# keyDuino_v5_rev1.net
KiCad netlist of a schematic drawn in EAGLE
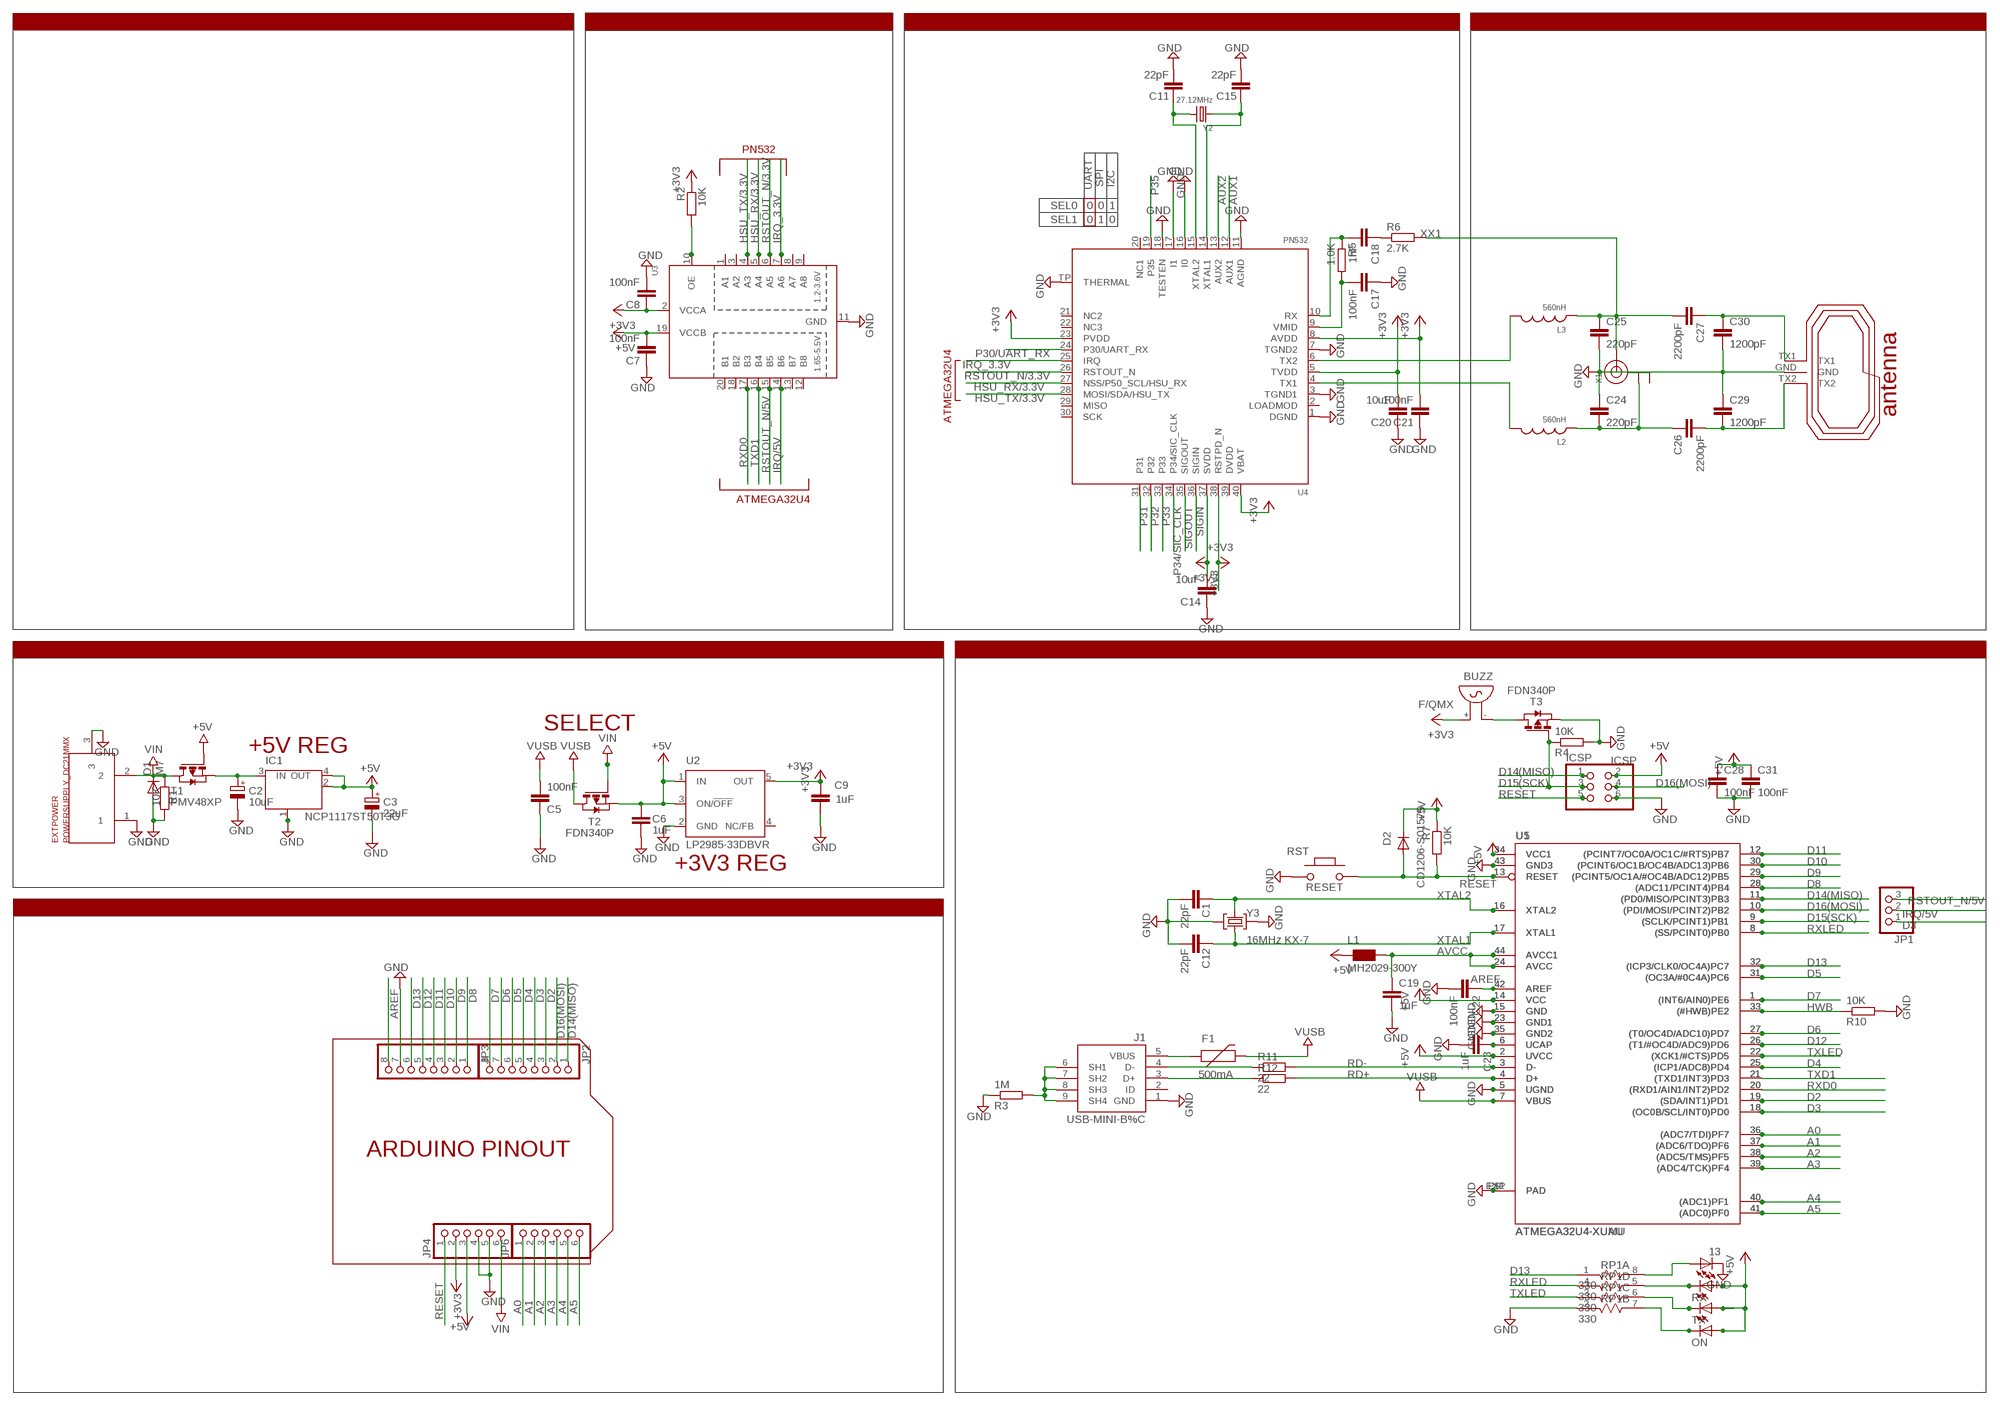
[diagram p0: schematic, sheet 1]

(export (version "E")
  (design (tool "Eeschema 10.0.6"))
  (components
    (comp (ref "13")
      (value "LEDCHIPLED_0603")
      (footprint "eagle-import:CHIPLED_0603")
      (libsource (lib "eagle-import") (part "LEDCHIPLED_0603"))
    )
    (comp (ref "BUZZ")
      (value "F/QMX")
      (footprint "eagle-import:F_QMX")
      (libsource (lib "eagle-import") (part "F/QMX"))
    )
    (comp (ref "C1")
      (value "22pF")
      (footprint "eagle-import:0603-CAP")
      (libsource (lib "eagle-import") (part "CAP0603-CAP"))
    )
    (comp (ref "C2")
      (value "10uF")
      (footprint "eagle-import:SMC_B")
      (libsource (lib "eagle-import") (part "CPOL-EUSMCB"))
    )
    (comp (ref "C3")
      (value "22uF")
      (footprint "eagle-import:SMC_B")
      (libsource (lib "eagle-import") (part "CPOL-EUSMCB"))
    )
    (comp (ref "C5")
      (value "100nF")
      (footprint "eagle-import:C0603")
      (libsource (lib "eagle-import") (part "resistor_C-EUC0603"))
    )
    (comp (ref "C6")
      (value "1uF")
      (footprint "eagle-import:C0603")
      (libsource (lib "eagle-import") (part "C-EUC0603"))
    )
    (comp (ref "C7")
      (value "100nF")
      (footprint "eagle-import:C0603")
      (libsource (lib "eagle-import") (part "C-EUC0603"))
    )
    (comp (ref "C8")
      (value "100nF")
      (footprint "eagle-import:C0603")
      (libsource (lib "eagle-import") (part "C-EUC0603"))
    )
    (comp (ref "C9")
      (value "1uF")
      (footprint "eagle-import:C0603")
      (libsource (lib "eagle-import") (part "C-EUC0603"))
    )
    (comp (ref "C11")
      (value "22pF")
      (footprint "eagle-import:0603-CAP")
      (libsource (lib "eagle-import") (part "CAP0603-CAP"))
    )
    (comp (ref "C12")
      (value "22pF")
      (footprint "eagle-import:0603-CAP")
      (libsource (lib "eagle-import") (part "CAP0603-CAP"))
    )
    (comp (ref "C14")
      (value "10uF")
      (footprint "eagle-import:C0805")
      (libsource (lib "eagle-import") (part "C-EUC0805"))
    )
    (comp (ref "C15")
      (value "22pF")
      (footprint "eagle-import:0603-CAP")
      (libsource (lib "eagle-import") (part "CAP0603-CAP"))
    )
    (comp (ref "C17")
      (value "100nF")
      (footprint "eagle-import:C0603")
      (libsource (lib "eagle-import") (part "C-EUC0603"))
    )
    (comp (ref "C18")
      (value "1nF")
      (footprint "eagle-import:C0603")
      (libsource (lib "eagle-import") (part "C-EUC0603"))
    )
    (comp (ref "C19")
      (value "1uF")
      (footprint "eagle-import:C0603")
      (libsource (lib "eagle-import") (part "resistor_C-EUC0603"))
    )
    (comp (ref "C20")
      (value "10uF")
      (footprint "eagle-import:C0805")
      (libsource (lib "eagle-import") (part "C-EUC0805"))
    )
    (comp (ref "C21")
      (value "100nF")
      (footprint "eagle-import:C0805")
      (libsource (lib "eagle-import") (part "C-EUC0805"))
    )
    (comp (ref "C22")
      (value "100nF")
      (footprint "eagle-import:C0603")
      (libsource (lib "eagle-import") (part "resistor_C-EUC0603"))
    )
    (comp (ref "C23")
      (value "1uF")
      (footprint "eagle-import:C0603")
      (libsource (lib "eagle-import") (part "resistor_C-EUC0603"))
    )
    (comp (ref "C24")
      (value "220pF")
      (footprint "eagle-import:C0603")
      (libsource (lib "eagle-import") (part "C-EUC0603"))
    )
    (comp (ref "C25")
      (value "220pF")
      (footprint "eagle-import:C0603")
      (libsource (lib "eagle-import") (part "C-EUC0603"))
    )
    (comp (ref "C26")
      (value "2200pF")
      (footprint "eagle-import:C0603")
      (libsource (lib "eagle-import") (part "C-EUC0603"))
    )
    (comp (ref "C27")
      (value "2200pF")
      (footprint "eagle-import:C0603")
      (libsource (lib "eagle-import") (part "C-EUC0603"))
    )
    (comp (ref "C28")
      (value "100nF")
      (footprint "eagle-import:C0603")
      (libsource (lib "eagle-import") (part "resistor_C-EUC0603"))
    )
    (comp (ref "C29")
      (value "1200pF")
      (footprint "eagle-import:C0603")
      (libsource (lib "eagle-import") (part "C-EUC0603"))
    )
    (comp (ref "C30")
      (value "1200pF")
      (footprint "eagle-import:C0603")
      (libsource (lib "eagle-import") (part "C-EUC0603"))
    )
    (comp (ref "C31")
      (value "100nF")
      (footprint "eagle-import:C0603")
      (libsource (lib "eagle-import") (part "resistor_C-EUC0603"))
    )
    (comp (ref "D1")
      (value "M7")
      (footprint "eagle-import:SMB")
      (libsource (lib "eagle-import") (part "DIODE-SMB"))
    )
    (comp (ref "D2")
      (value "CD1206-S01575")
      (footprint "eagle-import:MINIMELF")
      (libsource (lib "eagle-import") (part "DIODE-MINIMELF"))
    )
    (comp (ref "EXTPOWER")
      (value "POWERSUPPLY_DC21MMX")
      (footprint "eagle-import:POWERSUPPLY_DC-21MM")
      (libsource (lib "eagle-import") (part "POWERSUPPLY_DC21MMX"))
    )
    (comp (ref "F1")
      (value "500mA")
      (footprint "eagle-import:PTC-1206")
      (libsource (lib "eagle-import") (part "PTCSMD"))
    )
    (comp (ref "IC1")
      (value "NCP1117ST50T3G")
      (footprint "eagle-import:SOT223")
      (libsource (lib "eagle-import") (part "MC33269ST-3.3T3"))
    )
    (comp (ref "ICSP")
      (value "ICSP")
      (footprint "eagle-import:2X03")
      (libsource (lib "eagle-import") (part "PINHD-2X3"))
    )
    (comp (ref "J1")
      (value "USB-MINI-B%C")
      (footprint "eagle-import:USB-MINI-B_2")
      (libsource (lib "eagle-import") (part "USB-MINI-B%C"))
    )
    (comp (ref "JP1")
      (value "PINHD-1X3")
      (footprint "eagle-import:1X03")
      (libsource (lib "eagle-import") (part "PINHD-1X3"))
    )
    (comp (ref "JP2")
      (value "PINHD-1X8CLEANBIG")
      (footprint "eagle-import:1X08-CLEANBIG")
      (libsource (lib "eagle-import") (part "PINHD-1X8CLEANBIG"))
    )
    (comp (ref "JP3")
      (value "PINHD-1X8CLEANBIG")
      (footprint "eagle-import:1X08-CLEANBIG")
      (libsource (lib "eagle-import") (part "PINHD-1X8CLEANBIG"))
    )
    (comp (ref "JP4")
      (value "PINHD-1X6CB")
      (footprint "eagle-import:1X06-CLEANBIG")
      (libsource (lib "eagle-import") (part "PINHD-1X6CB"))
    )
    (comp (ref "JP6")
      (value "PINHD-1X6CB")
      (footprint "eagle-import:1X06-CLEANBIG")
      (libsource (lib "eagle-import") (part "PINHD-1X6CB"))
    )
    (comp (ref "L1")
      (value "MH2029-300Y")
      (footprint "eagle-import:0805")
      (libsource (lib "eagle-import") (part "WE-CBF_0805"))
    )
    (comp (ref "L2")
      (value "560nH")
      (footprint "eagle-import:0805@1")
      (libsource (lib "eagle-import") (part "INDUCTOR0805"))
    )
    (comp (ref "L3")
      (value "560nH")
      (footprint "eagle-import:0805@1")
      (libsource (lib "eagle-import") (part "INDUCTOR0805"))
    )
    (comp (ref "ON")
      (value "LEDCHIPLED_0603")
      (footprint "eagle-import:CHIPLED_0603")
      (libsource (lib "eagle-import") (part "LEDCHIPLED_0603"))
    )
    (comp (ref "R1")
      (value "10K")
      (footprint "eagle-import:R0603")
      (libsource (lib "eagle-import") (part "resistor_R-EU_R0603"))
    )
    (comp (ref "R2")
      (value "10K")
      (footprint "eagle-import:R0603")
      (libsource (lib "eagle-import") (part "R-EU_R0603"))
    )
    (comp (ref "R3")
      (value "1M")
      (footprint "eagle-import:R0805")
      (libsource (lib "eagle-import") (part "R-EU_R0805"))
    )
    (comp (ref "R4")
      (value "10K")
      (footprint "eagle-import:R0603")
      (libsource (lib "eagle-import") (part "R-EU_R0603"))
    )
    (comp (ref "R5")
      (value "1.0K")
      (footprint "eagle-import:R0603")
      (libsource (lib "eagle-import") (part "R-EU_R0603"))
    )
    (comp (ref "R6")
      (value "2.7K")
      (footprint "eagle-import:R0603")
      (libsource (lib "eagle-import") (part "R-EU_R0603"))
    )
    (comp (ref "R7")
      (value "10K")
      (footprint "eagle-import:R0603")
      (libsource (lib "eagle-import") (part "R-EU_R0603"))
    )
    (comp (ref "R10")
      (value "10K")
      (footprint "eagle-import:R0603")
      (libsource (lib "eagle-import") (part "R-EU_R0603"))
    )
    (comp (ref "R11")
      (value "22")
      (footprint "eagle-import:R0603")
      (libsource (lib "eagle-import") (part "R-EU_R0603"))
    )
    (comp (ref "R12")
      (value "22")
      (footprint "eagle-import:R0603")
      (libsource (lib "eagle-import") (part "R-EU_R0603"))
    )
    (comp (ref "RP1")
      (value "330")
      (footprint "eagle-import:RES4NT")
      (libsource (lib "eagle-import") (part "RES4NT"))
    )
    (comp (ref "RST")
      (value "RESET")
      (footprint "eagle-import:157SW")
      (libsource (lib "eagle-import") (part "PB157"))
    )
    (comp (ref "RX")
      (value "LEDCHIPLED_0603")
      (footprint "eagle-import:CHIPLED_0603")
      (libsource (lib "eagle-import") (part "LEDCHIPLED_0603"))
    )
    (comp (ref "T1")
      (value "PMV48XP")
      (footprint "eagle-import:SOT-23")
      (libsource (lib "eagle-import") (part "PMOSSOT23"))
    )
    (comp (ref "T2")
      (value "FDN340P")
      (footprint "eagle-import:SOT-23")
      (libsource (lib "eagle-import") (part "PMOSSOT23"))
    )
    (comp (ref "T3")
      (value "FDN340P")
      (footprint "eagle-import:SOT-23")
      (libsource (lib "eagle-import") (part "PMOSSOT23"))
    )
    (comp (ref "TX")
      (value "LEDCHIPLED_0603")
      (footprint "eagle-import:CHIPLED_0603")
      (libsource (lib "eagle-import") (part "LEDCHIPLED_0603"))
    )
    (comp (ref "U$1")
      (value "ANT_V3")
      (footprint "eagle-import:ANT_13.56_P4")
      (libsource (lib "eagle-import") (part "ANT_V3"))
    )
    (comp (ref "U1")
      (value "ATMEGA32U4-XUAU")
      (footprint "eagle-import:TQFP44-PAD")
      (libsource (lib "eagle-import") (part "ATMEGA32U4-XUAU"))
    )
    (comp (ref "U2")
      (value "LP2985-33DBVR")
      (footprint "eagle-import:SOT23-DBV")
      (libsource (lib "eagle-import") (part "LP2985-XXDBVR33"))
    )
    (comp (ref "U3")
      (value "TXB0108PWR")
      (footprint "eagle-import:TSSOP20")
      (libsource (lib "eagle-import") (part "TXB0108PWR"))
    )
    (comp (ref "U4")
      (value "PN532")
      (footprint "eagle-import:HVQFN40-6X6")
      (libsource (lib "eagle-import") (part "PN532"))
    )
    (comp (ref "U5")
      (value "ATMEGA32U4-XUMU")
      (footprint "eagle-import:QFN44ML7X7")
      (libsource (lib "eagle-import") (part "ATMEGA32U4-XUMU"))
    )
    (comp (ref "X1")
      (value "ANTENNA_U.FL")
      (footprint "eagle-import:U.FL")
      (libsource (lib "eagle-import") (part "ANTENNA_U.FL"))
    )
    (comp (ref "Y2")
      (value "27.12MHz")
      (footprint "eagle-import:CRYSTAL_3.2X2.5")
      (libsource (lib "eagle-import") (part "CRYSTALTHIN"))
    )
    (comp (ref "Y3")
      (value "16MHz KX-7")
      (footprint "eagle-import:CRYSTAL-3.2-2.5")
      (libsource (lib "eagle-import") (part "CRYSTAL-3.2-2.5"))
    )
  )
  (nets
    (net (code "1") (name "+3V3") (class "Default")
      (node (ref "BUZZ") (pin "+") (pinfunction "2_+") (pintype "passive"))
      (node (ref "C14") (pin "2") (pinfunction "2_2") (pintype "passive"))
      (node (ref "C20") (pin "2") (pinfunction "2_2") (pintype "passive"))
      (node (ref "C21") (pin "2") (pinfunction "2_2") (pintype "passive"))
      (node (ref "C8") (pin "1") (pinfunction "1_1") (pintype "passive"))
      (node (ref "C9") (pin "2") (pinfunction "2_2") (pintype "passive"))
      (node (ref "JP4") (pin "2") (pinfunction "2_2") (pintype "passive"))
      (node (ref "R2") (pin "1") (pinfunction "1_1") (pintype "passive"))
      (node (ref "U2") (pin "5") (pinfunction "OUT_5") (pintype "passive"))
      (node (ref "U3") (pin "2") (pinfunction "VCCA_2") (pintype "bidirectional"))
      (node (ref "U4") (pin "23") (pinfunction "PVDD_23") (pintype "bidirectional"))
      (node (ref "U4") (pin "37") (pinfunction "SVDD_37") (pintype "bidirectional"))
      (node (ref "U4") (pin "38") (pinfunction "RSTPD_N_38") (pintype "bidirectional"))
      (node (ref "U4") (pin "40") (pinfunction "VBAT_40") (pintype "bidirectional"))
      (node (ref "U4") (pin "5") (pinfunction "TVDD_5") (pintype "bidirectional"))
      (node (ref "U4") (pin "8") (pinfunction "AVDD_8") (pintype "bidirectional"))
    )
    (net (code "2") (name "+5V") (class "Default")
      (node (ref "C28") (pin "1") (pinfunction "1_1") (pintype "passive"))
      (node (ref "C3") (pin "+") (pinfunction "+_+") (pintype "passive"))
      (node (ref "C31") (pin "1") (pinfunction "1_1") (pintype "passive"))
      (node (ref "C6") (pin "2") (pinfunction "2_2") (pintype "passive"))
      (node (ref "C7") (pin "2") (pinfunction "2_2") (pintype "passive"))
      (node (ref "D2") (pin "C") (pinfunction "C_C") (pintype "passive"))
      (node (ref "IC1") (pin "2") (pinfunction "OUT_2") (pintype "passive"))
      (node (ref "IC1") (pin "4") (pinfunction "OUT_4") (pintype "passive"))
      (node (ref "ICSP") (pin "2") (pinfunction "2_2") (pintype "passive"))
      (node (ref "JP4") (pin "3") (pinfunction "3_3") (pintype "passive"))
      (node (ref "L1") (pin "1") (pinfunction "1_1") (pintype "passive"))
      (node (ref "ON") (pin "A") (pinfunction "A_A") (pintype "passive"))
      (node (ref "R7") (pin "1") (pinfunction "1_1") (pintype "passive"))
      (node (ref "RX") (pin "A") (pinfunction "A_A") (pintype "passive"))
      (node (ref "T1") (pin "3") (pinfunction "G_3") (pintype "passive"))
      (node (ref "T2") (pin "2") (pinfunction "S_2") (pintype "passive"))
      (node (ref "TX") (pin "A") (pinfunction "A_A") (pintype "passive"))
      (node (ref "U1") (pin "14") (pinfunction "VCC_14") (pintype "power_in"))
      (node (ref "U1") (pin "2") (pinfunction "UVCC_2") (pintype "power_in"))
      (node (ref "U1") (pin "34") (pinfunction "VCC1_34") (pintype "power_in"))
      (node (ref "U2") (pin "1") (pinfunction "IN_1") (pintype "input"))
      (node (ref "U2") (pin "3") (pinfunction "ON/~{OFF}_3") (pintype "input"))
      (node (ref "U3") (pin "19") (pinfunction "VCCB_19") (pintype "bidirectional"))
      (node (ref "U5") (pin "14") (pinfunction "VCC_14") (pintype "power_in"))
      (node (ref "U5") (pin "2") (pinfunction "UVCC_2") (pintype "power_in"))
      (node (ref "U5") (pin "34") (pinfunction "VCC1_34") (pintype "power_in"))
    )
    (net (code "3") (name "/A0") (class "Default")
      (node (ref "JP6") (pin "1") (pinfunction "1_1") (pintype "passive"))
      (node (ref "U1") (pin "36") (pinfunction "(ADC7/TDI)PF7_36") (pintype "bidirectional"))
      (node (ref "U5") (pin "36") (pinfunction "(ADC7/TDI)PF7_36") (pintype "bidirectional"))
    )
    (net (code "4") (name "/A1") (class "Default")
      (node (ref "JP6") (pin "2") (pinfunction "2_2") (pintype "passive"))
      (node (ref "U1") (pin "37") (pinfunction "(ADC6/TDO)PF6_37") (pintype "bidirectional"))
      (node (ref "U5") (pin "37") (pinfunction "(ADC6/TDO)PF6_37") (pintype "bidirectional"))
    )
    (net (code "5") (name "/A2") (class "Default")
      (node (ref "JP6") (pin "3") (pinfunction "3_3") (pintype "passive"))
      (node (ref "U1") (pin "38") (pinfunction "(ADC5/TMS)PF5_38") (pintype "bidirectional"))
      (node (ref "U5") (pin "38") (pinfunction "(ADC5/TMS)PF5_38") (pintype "bidirectional"))
    )
    (net (code "6") (name "/A3") (class "Default")
      (node (ref "JP6") (pin "4") (pinfunction "4_4") (pintype "passive"))
      (node (ref "U1") (pin "39") (pinfunction "(ADC4/TCK)PF4_39") (pintype "bidirectional"))
      (node (ref "U5") (pin "39") (pinfunction "(ADC4/TCK)PF4_39") (pintype "bidirectional"))
    )
    (net (code "7") (name "/A4") (class "Default")
      (node (ref "JP6") (pin "5") (pinfunction "5_5") (pintype "passive"))
      (node (ref "U1") (pin "40") (pinfunction "(ADC1)PF1_40") (pintype "bidirectional"))
      (node (ref "U5") (pin "40") (pinfunction "(ADC1)PF1_40") (pintype "bidirectional"))
    )
    (net (code "8") (name "/A5") (class "Default")
      (node (ref "JP6") (pin "6") (pinfunction "6_6") (pintype "passive"))
      (node (ref "U1") (pin "41") (pinfunction "(ADC0)PF0_41") (pintype "bidirectional"))
      (node (ref "U5") (pin "41") (pinfunction "(ADC0)PF0_41") (pintype "bidirectional"))
    )
    (net (code "9") (name "/AREF") (class "Default")
      (node (ref "C22") (pin "1") (pinfunction "1_1") (pintype "passive"))
      (node (ref "JP3") (pin "8") (pinfunction "8_8") (pintype "passive"))
      (node (ref "U1") (pin "42") (pinfunction "AREF_42") (pintype "power_in"))
      (node (ref "U5") (pin "42") (pinfunction "AREF_42") (pintype "power_in"))
    )
    (net (code "10") (name "/AUX1") (class "Default")
      (node (ref "U4") (pin "12") (pinfunction "AUX1_12") (pintype "bidirectional"))
    )
    (net (code "11") (name "/AUX2") (class "Default")
      (node (ref "U4") (pin "13") (pinfunction "AUX2_13") (pintype "bidirectional"))
    )
    (net (code "12") (name "/AVCC") (class "Default")
      (node (ref "C19") (pin "1") (pinfunction "1_1") (pintype "passive"))
      (node (ref "L1") (pin "2") (pinfunction "2_2") (pintype "passive"))
      (node (ref "U1") (pin "24") (pinfunction "AVCC_24") (pintype "power_in"))
      (node (ref "U1") (pin "44") (pinfunction "AVCC1_44") (pintype "power_in"))
      (node (ref "U5") (pin "24") (pinfunction "AVCC_24") (pintype "power_in"))
      (node (ref "U5") (pin "44") (pinfunction "AVCC1_44") (pintype "power_in"))
    )
    (net (code "13") (name "/D2") (class "Default")
      (node (ref "JP2") (pin "3") (pinfunction "3_3") (pintype "passive"))
      (node (ref "U1") (pin "19") (pinfunction "(SDA/INT1)PD1_19") (pintype "bidirectional"))
      (node (ref "U5") (pin "19") (pinfunction "(SDA/INT1)PD1_19") (pintype "bidirectional"))
    )
    (net (code "14") (name "/D3") (class "Default")
      (node (ref "JP1") (pin "1") (pinfunction "1_1") (pintype "passive"))
      (node (ref "JP2") (pin "4") (pinfunction "4_4") (pintype "passive"))
      (node (ref "U1") (pin "18") (pinfunction "(OC0B/SCL/INT0)PD0_18") (pintype "bidirectional"))
      (node (ref "U5") (pin "18") (pinfunction "(OC0B/SCL/INT0)PD0_18") (pintype "bidirectional"))
    )
    (net (code "15") (name "/D4") (class "Default")
      (node (ref "JP2") (pin "5") (pinfunction "5_5") (pintype "passive"))
      (node (ref "U1") (pin "25") (pinfunction "(ICP1/ADC8)PD4_25") (pintype "bidirectional"))
      (node (ref "U5") (pin "25") (pinfunction "(ICP1/ADC8)PD4_25") (pintype "bidirectional"))
    )
    (net (code "16") (name "/D5") (class "Default")
      (node (ref "JP2") (pin "6") (pinfunction "6_6") (pintype "passive"))
      (node (ref "U1") (pin "31") (pinfunction "(OC3A/#0C4A)PC6_31") (pintype "bidirectional"))
      (node (ref "U5") (pin "31") (pinfunction "(OC3A/#0C4A)PC6_31") (pintype "bidirectional"))
    )
    (net (code "17") (name "/D6") (class "Default")
      (node (ref "JP2") (pin "7") (pinfunction "7_7") (pintype "passive"))
      (node (ref "U1") (pin "27") (pinfunction "(T0/OC4D/ADC10)PD7_27") (pintype "bidirectional"))
      (node (ref "U5") (pin "27") (pinfunction "(T0/OC4D/ADC10)PD7_27") (pintype "bidirectional"))
    )
    (net (code "18") (name "/D7") (class "Default")
      (node (ref "JP2") (pin "8") (pinfunction "8_8") (pintype "passive"))
      (node (ref "U1") (pin "1") (pinfunction "(INT6/AIN0)PE6_1") (pintype "bidirectional"))
      (node (ref "U5") (pin "1") (pinfunction "(INT6/AIN0)PE6_1") (pintype "bidirectional"))
    )
    (net (code "19") (name "/D8") (class "Default")
      (node (ref "JP3") (pin "1") (pinfunction "1_1") (pintype "passive"))
      (node (ref "U1") (pin "28") (pinfunction "(ADC11/PCINT4)PB4_28") (pintype "bidirectional"))
      (node (ref "U5") (pin "28") (pinfunction "(ADC11/PCINT4)PB4_28") (pintype "bidirectional"))
    )
    (net (code "20") (name "/D9") (class "Default")
      (node (ref "JP3") (pin "2") (pinfunction "2_2") (pintype "passive"))
      (node (ref "U1") (pin "29") (pinfunction "(PCINT5/OC1A/#OC4B/ADC12)PB5_29") (pintype "bidirectional"))
      (node (ref "U5") (pin "29") (pinfunction "(PCINT5/OC1A/#OC4B/ADC12)PB5_29") (pintype "bidirectional"))
    )
    (net (code "21") (name "/D10") (class "Default")
      (node (ref "JP3") (pin "3") (pinfunction "3_3") (pintype "passive"))
      (node (ref "U1") (pin "30") (pinfunction "(PCINT6/OC1B/OC4B/ADC13)PB6_30") (pintype "bidirectional"))
      (node (ref "U5") (pin "30") (pinfunction "(PCINT6/OC1B/OC4B/ADC13)PB6_30") (pintype "bidirectional"))
    )
    (net (code "22") (name "/D11") (class "Default")
      (node (ref "JP3") (pin "4") (pinfunction "4_4") (pintype "passive"))
      (node (ref "U1") (pin "12") (pinfunction "(PCINT7/OC0A/OC1C/#RTS)PB7_12") (pintype "bidirectional"))
      (node (ref "U5") (pin "12") (pinfunction "(PCINT7/OC0A/OC1C/#RTS)PB7_12") (pintype "bidirectional"))
    )
    (net (code "23") (name "/D12") (class "Default")
      (node (ref "JP3") (pin "5") (pinfunction "5_5") (pintype "passive"))
      (node (ref "U1") (pin "26") (pinfunction "(T1/#OC4D/ADC9)PD6_26") (pintype "bidirectional"))
      (node (ref "U5") (pin "26") (pinfunction "(T1/#OC4D/ADC9)PD6_26") (pintype "bidirectional"))
    )
    (net (code "24") (name "/D13") (class "Default")
      (node (ref "JP3") (pin "6") (pinfunction "6_6") (pintype "passive"))
      (node (ref "RP1") (pin "1") (pinfunction "1_1") (pintype "passive"))
      (node (ref "U1") (pin "32") (pinfunction "(ICP3/CLK0/OC4A)PC7_32") (pintype "bidirectional"))
      (node (ref "U5") (pin "32") (pinfunction "(ICP3/CLK0/OC4A)PC7_32") (pintype "bidirectional"))
    )
    (net (code "25") (name "/D14(MISO)") (class "Default")
      (node (ref "ICSP") (pin "1") (pinfunction "1_1") (pintype "passive"))
      (node (ref "JP2") (pin "1") (pinfunction "1_1") (pintype "passive"))
      (node (ref "U1") (pin "11") (pinfunction "(PD0/MISO/PCINT3)PB3_11") (pintype "bidirectional"))
      (node (ref "U5") (pin "11") (pinfunction "(PD0/MISO/PCINT3)PB3_11") (pintype "bidirectional"))
    )
    (net (code "26") (name "/D15(SCK)") (class "Default")
      (node (ref "ICSP") (pin "3") (pinfunction "3_3") (pintype "passive"))
      (node (ref "R4") (pin "1") (pinfunction "1_1") (pintype "passive"))
      (node (ref "T3") (pin "3") (pinfunction "G_3") (pintype "passive"))
      (node (ref "U1") (pin "9") (pinfunction "(SCLK/PCINT1)PB1_9") (pintype "bidirectional"))
      (node (ref "U5") (pin "9") (pinfunction "(SCLK/PCINT1)PB1_9") (pintype "bidirectional"))
    )
    (net (code "27") (name "/D16(MOSI)") (class "Default")
      (node (ref "ICSP") (pin "4") (pinfunction "4_4") (pintype "passive"))
      (node (ref "JP2") (pin "2") (pinfunction "2_2") (pintype "passive"))
      (node (ref "U1") (pin "10") (pinfunction "(PDI/MOSI/PCINT2)PB2_10") (pintype "bidirectional"))
      (node (ref "U5") (pin "10") (pinfunction "(PDI/MOSI/PCINT2)PB2_10") (pintype "bidirectional"))
    )
    (net (code "28") (name "/HSU_RX{slash}3.3V") (class "Default")
      (node (ref "U3") (pin "5") (pinfunction "A4_5") (pintype "bidirectional"))
      (node (ref "U4") (pin "27") (pinfunction "NSS/P50_SCL/HSU_RX_27") (pintype "bidirectional"))
    )
    (net (code "29") (name "/HSU_TX{slash}3.3V") (class "Default")
      (node (ref "U3") (pin "4") (pinfunction "A3_4") (pintype "bidirectional"))
      (node (ref "U4") (pin "28") (pinfunction "MOSI/SDA/HSU_TX_28") (pintype "bidirectional"))
    )
    (net (code "30") (name "/HWB") (class "Default")
      (node (ref "R10") (pin "1") (pinfunction "1_1") (pintype "passive"))
      (node (ref "U1") (pin "33") (pinfunction "(#HWB)PE2_33") (pintype "bidirectional"))
      (node (ref "U5") (pin "33") (pinfunction "(#HWB)PE2_33") (pintype "bidirectional"))
    )
    (net (code "31") (name "/IRQ_3.3V") (class "Default")
      (node (ref "U3") (pin "7") (pinfunction "A6_7") (pintype "bidirectional"))
      (node (ref "U4") (pin "25") (pinfunction "IRQ_25") (pintype "bidirectional"))
    )
    (net (code "32") (name "/IRQ{slash}5V") (class "Default")
      (node (ref "JP1") (pin "2") (pinfunction "2_2") (pintype "passive"))
      (node (ref "U3") (pin "14") (pinfunction "B6_14") (pintype "bidirectional"))
    )
    (net (code "33") (name "/P30{slash}UART_RX") (class "Default")
      (node (ref "U4") (pin "24") (pinfunction "P30/UART_RX_24") (pintype "bidirectional"))
    )
    (net (code "34") (name "/P31") (class "Default")
      (node (ref "U4") (pin "31") (pinfunction "P31_31") (pintype "bidirectional"))
    )
    (net (code "35") (name "/P32") (class "Default")
      (node (ref "U4") (pin "32") (pinfunction "P32_32") (pintype "bidirectional"))
    )
    (net (code "36") (name "/P33") (class "Default")
      (node (ref "U4") (pin "33") (pinfunction "P33_33") (pintype "bidirectional"))
    )
    (net (code "37") (name "/P34{slash}SIC_CLK") (class "Default")
      (node (ref "U4") (pin "34") (pinfunction "P34/SIC_CLK_34") (pintype "bidirectional"))
    )
    (net (code "38") (name "/P35") (class "Default")
      (node (ref "U4") (pin "19") (pinfunction "P35_19") (pintype "bidirectional"))
    )
    (net (code "39") (name "/RD+") (class "Default")
      (node (ref "R12") (pin "2") (pinfunction "2_2") (pintype "passive"))
      (node (ref "U1") (pin "4") (pinfunction "D+_4") (pintype "bidirectional"))
      (node (ref "U5") (pin "4") (pinfunction "D+_4") (pintype "bidirectional"))
    )
    (net (code "40") (name "/RD-") (class "Default")
      (node (ref "R11") (pin "2") (pinfunction "2_2") (pintype "passive"))
      (node (ref "U1") (pin "3") (pinfunction "D-_3") (pintype "bidirectional"))
      (node (ref "U5") (pin "3") (pinfunction "D-_3") (pintype "bidirectional"))
    )
    (net (code "41") (name "/RESET") (class "Default")
      (node (ref "D2") (pin "A") (pinfunction "A_A") (pintype "passive"))
      (node (ref "ICSP") (pin "5") (pinfunction "5_5") (pintype "passive"))
      (node (ref "JP4") (pin "1") (pinfunction "1_1") (pintype "passive"))
      (node (ref "R7") (pin "2") (pinfunction "2_2") (pintype "passive"))
      (node (ref "RST") (pin "2") (pinfunction "2_2") (pintype "passive"))
      (node (ref "U1") (pin "13") (pinfunction "RESET_13") (pintype "input"))
      (node (ref "U5") (pin "13") (pinfunction "RESET_13") (pintype "input"))
    )
    (net (code "42") (name "/RSTOUT_N{slash}3.3V") (class "Default")
      (node (ref "U3") (pin "6") (pinfunction "A5_6") (pintype "bidirectional"))
      (node (ref "U4") (pin "26") (pinfunction "RSTOUT_N_26") (pintype "bidirectional"))
    )
    (net (code "43") (name "/RSTOUT_N{slash}5V") (class "Default")
      (node (ref "JP1") (pin "3") (pinfunction "3_3") (pintype "passive"))
      (node (ref "U3") (pin "15") (pinfunction "B5_15") (pintype "bidirectional"))
    )
    (net (code "44") (name "/RXD0") (class "Default")
      (node (ref "U1") (pin "20") (pinfunction "(RXD1/AIN1/INT2)PD2_20") (pintype "bidirectional"))
      (node (ref "U3") (pin "17") (pinfunction "B3_17") (pintype "bidirectional"))
      (node (ref "U5") (pin "20") (pinfunction "(RXD1/AIN1/INT2)PD2_20") (pintype "bidirectional"))
    )
    (net (code "45") (name "/RXLED") (class "Default")
      (node (ref "RP1") (pin "4") (pinfunction "1_4") (pintype "passive"))
      (node (ref "U1") (pin "8") (pinfunction "(SS/PCINT0)PB0_8") (pintype "bidirectional"))
      (node (ref "U5") (pin "8") (pinfunction "(SS/PCINT0)PB0_8") (pintype "bidirectional"))
    )
    (net (code "46") (name "/SIGIN") (class "Default")
      (node (ref "U4") (pin "36") (pinfunction "SIGIN_36") (pintype "bidirectional"))
    )
    (net (code "47") (name "/SIGOUT") (class "Default")
      (node (ref "U4") (pin "35") (pinfunction "SIGOUT_35") (pintype "bidirectional"))
    )
    (net (code "48") (name "/TXD1") (class "Default")
      (node (ref "U1") (pin "21") (pinfunction "(TXD1/INT3)PD3_21") (pintype "bidirectional"))
      (node (ref "U3") (pin "16") (pinfunction "B4_16") (pintype "bidirectional"))
      (node (ref "U5") (pin "21") (pinfunction "(TXD1/INT3)PD3_21") (pintype "bidirectional"))
    )
    (net (code "49") (name "/TXLED") (class "Default")
      (node (ref "RP1") (pin "3") (pinfunction "1_3") (pintype "passive"))
      (node (ref "U1") (pin "22") (pinfunction "(XCK1/#CTS)PD5_22") (pintype "bidirectional"))
      (node (ref "U5") (pin "22") (pinfunction "(XCK1/#CTS)PD5_22") (pintype "bidirectional"))
    )
    (net (code "50") (name "/XTAL1") (class "Default")
      (node (ref "C12") (pin "2") (pinfunction "2_2") (pintype "passive"))
      (node (ref "U1") (pin "17") (pinfunction "XTAL1_17") (pintype "bidirectional"))
      (node (ref "U5") (pin "17") (pinfunction "XTAL1_17") (pintype "bidirectional"))
      (node (ref "Y3") (pin "1") (pinfunction "C1_1") (pintype "passive"))
    )
    (net (code "51") (name "/XTAL2") (class "Default")
      (node (ref "C1") (pin "2") (pinfunction "2_2") (pintype "passive"))
      (node (ref "U1") (pin "16") (pinfunction "XTAL2_16") (pintype "bidirectional"))
      (node (ref "U5") (pin "16") (pinfunction "XTAL2_16") (pintype "bidirectional"))
      (node (ref "Y3") (pin "3") (pinfunction "C2_3") (pintype "passive"))
    )
    (net (code "52") (name "/XX1") (class "Default")
      (node (ref "C25") (pin "1") (pinfunction "1_1") (pintype "passive"))
      (node (ref "C27") (pin "2") (pinfunction "2_2") (pintype "passive"))
      (node (ref "L3") (pin "1") (pinfunction "1_1") (pintype "passive"))
      (node (ref "R6") (pin "2") (pinfunction "2_2") (pintype "passive"))
      (node (ref "X1") (pin "3") (pinfunction "SIGNAL_3") (pintype "passive"))
    )
    (net (code "53") (name "GND") (class "Default")
      (node (ref "13") (pin "C") (pinfunction "C_C") (pintype "passive"))
      (node (ref "C1") (pin "1") (pinfunction "1_1") (pintype "passive"))
      (node (ref "C11") (pin "1") (pinfunction "1_1") (pintype "passive"))
      (node (ref "C12") (pin "1") (pinfunction "1_1") (pintype "passive"))
      (node (ref "C14") (pin "1") (pinfunction "1_1") (pintype "passive"))
      (node (ref "C15") (pin "1") (pinfunction "1_1") (pintype "passive"))
      (node (ref "C17") (pin "1") (pinfunction "1_1") (pintype "passive"))
      (node (ref "C19") (pin "2") (pinfunction "2_2") (pintype "passive"))
      (node (ref "C2") (pin "-") (pinfunction "-_-") (pintype "passive"))
      (node (ref "C20") (pin "1") (pinfunction "1_1") (pintype "passive"))
      (node (ref "C21") (pin "1") (pinfunction "1_1") (pintype "passive"))
      (node (ref "C22") (pin "2") (pinfunction "2_2") (pintype "passive"))
      (node (ref "C23") (pin "2") (pinfunction "2_2") (pintype "passive"))
      (node (ref "C24") (pin "1") (pinfunction "1_1") (pintype "passive"))
      (node (ref "C25") (pin "2") (pinfunction "2_2") (pintype "passive"))
      (node (ref "C28") (pin "2") (pinfunction "2_2") (pintype "passive"))
      (node (ref "C29") (pin "1") (pinfunction "1_1") (pintype "passive"))
      (node (ref "C3") (pin "-") (pinfunction "-_-") (pintype "passive"))
      (node (ref "C30") (pin "2") (pinfunction "2_2") (pintype "passive"))
      (node (ref "C31") (pin "2") (pinfunction "2_2") (pintype "passive"))
      (node (ref "C5") (pin "1") (pinfunction "1_1") (pintype "passive"))
      (node (ref "C6") (pin "1") (pinfunction "1_1") (pintype "passive"))
      (node (ref "C7") (pin "1") (pinfunction "1_1") (pintype "passive"))
      (node (ref "C8") (pin "2") (pinfunction "2_2") (pintype "passive"))
      (node (ref "C9") (pin "1") (pinfunction "1_1") (pintype "passive"))
      (node (ref "D1") (pin "A") (pinfunction "A_A") (pintype "passive"))
      (node (ref "EXTPOWER") (pin "1") (pinfunction "1_1") (pintype "power_in"))
      (node (ref "EXTPOWER") (pin "3") (pinfunction "3_3") (pintype "power_in"))
      (node (ref "IC1") (pin "1") (pinfunction "GND/ADJ_1") (pintype "input"))
      (node (ref "ICSP") (pin "6") (pinfunction "6_6") (pintype "passive"))
      (node (ref "J1") (pin "1") (pinfunction "GND_1") (pintype "passive"))
      (node (ref "JP3") (pin "7") (pinfunction "7_7") (pintype "passive"))
      (node (ref "JP4") (pin "4") (pinfunction "4_4") (pintype "passive"))
      (node (ref "JP4") (pin "5") (pinfunction "5_5") (pintype "passive"))
      (node (ref "R1") (pin "1") (pinfunction "1_1") (pintype "passive"))
      (node (ref "R10") (pin "2") (pinfunction "2_2") (pintype "passive"))
      (node (ref "R3") (pin "1") (pinfunction "1_1") (pintype "passive"))
      (node (ref "R4") (pin "2") (pinfunction "2_2") (pintype "passive"))
      (node (ref "RP1") (pin "2") (pinfunction "1_2") (pintype "passive"))
      (node (ref "RST") (pin "1") (pinfunction "1_1") (pintype "passive"))
      (node (ref "T3") (pin "2") (pinfunction "S_2") (pintype "passive"))
      (node (ref "U$1") (pin "GND") (pinfunction "GND_GND") (pintype "bidirectional"))
      (node (ref "U1") (pin "15") (pinfunction "GND_15") (pintype "power_in"))
      (node (ref "U1") (pin "23") (pinfunction "GND1_23") (pintype "power_in"))
      (node (ref "U1") (pin "35") (pinfunction "GND2_35") (pintype "power_in"))
      (node (ref "U1") (pin "43") (pinfunction "GND3_43") (pintype "power_in"))
      (node (ref "U1") (pin "5") (pinfunction "UGND_5") (pintype "power_in"))
      (node (ref "U1") (pin "P$1") (pinfunction "PAD_P$1") (pintype "power_in"))
      (node (ref "U2") (pin "2") (pinfunction "GND_2") (pintype "power_in"))
      (node (ref "U3") (pin "11") (pinfunction "GND_11") (pintype "bidirectional"))
      (node (ref "U4") (pin "1") (pinfunction "DGND_1") (pintype "bidirectional"))
      (node (ref "U4") (pin "11") (pinfunction "AGND_11") (pintype "bidirectional"))
      (node (ref "U4") (pin "16") (pinfunction "I0_16") (pintype "bidirectional"))
      (node (ref "U4") (pin "17") (pinfunction "I1_17") (pintype "bidirectional"))
      (node (ref "U4") (pin "18") (pinfunction "TESTEN_18") (pintype "bidirectional"))
      (node (ref "U4") (pin "3") (pinfunction "TGND1_3") (pintype "bidirectional"))
      (node (ref "U4") (pin "7") (pinfunction "TGND2_7") (pintype "bidirectional"))
      (node (ref "U4") (pin "TP") (pinfunction "THERMAL_TP") (pintype "bidirectional"))
      (node (ref "U5") (pin "15") (pinfunction "GND_15") (pintype "power_in"))
      (node (ref "U5") (pin "23") (pinfunction "GND1_23") (pintype "power_in"))
      (node (ref "U5") (pin "35") (pinfunction "GND2_35") (pintype "power_in"))
      (node (ref "U5") (pin "43") (pinfunction "GND3_43") (pintype "power_in"))
      (node (ref "U5") (pin "5") (pinfunction "UGND_5") (pintype "power_in"))
      (node (ref "U5") (pin "EXP") (pinfunction "PAD_EXP") (pintype "power_in"))
      (node (ref "Y3") (pin "2") (pinfunction "GND_2") (pintype "passive"))
      (node (ref "Y3") (pin "4") (pinfunction "GND_4") (pintype "passive"))
    )
    (net (code "54") (name "Net-(BUZZ-1)") (class "Default")
      (node (ref "BUZZ") (pin "-") (pinfunction "1_-") (pintype "passive"))
      (node (ref "T3") (pin "1") (pinfunction "D_1") (pintype "passive"))
    )
    (net (code "55") (name "Net-(C18-Pad1)") (class "Default")
      (node (ref "C18") (pin "1") (pinfunction "1_1") (pintype "passive"))
      (node (ref "R6") (pin "1") (pinfunction "1_1") (pintype "passive"))
    )
    (net (code "56") (name "Net-(C24-Pad2)") (class "Default")
      (node (ref "C24") (pin "2") (pinfunction "2_2") (pintype "passive"))
      (node (ref "C26") (pin "1") (pinfunction "1_1") (pintype "passive"))
      (node (ref "L2") (pin "1") (pinfunction "1_1") (pintype "passive"))
      (node (ref "X1") (pin "1") (pinfunction "GND_1") (pintype "passive"))
    )
    (net (code "57") (name "Net-(C26-Pad2)") (class "Default")
      (node (ref "C26") (pin "2") (pinfunction "2_2") (pintype "passive"))
      (node (ref "C29") (pin "2") (pinfunction "2_2") (pintype "passive"))
      (node (ref "U$1") (pin "TX2") (pinfunction "TX2_TX2") (pintype "bidirectional"))
    )
    (net (code "58") (name "Net-(C27-Pad1)") (class "Default")
      (node (ref "C27") (pin "1") (pinfunction "1_1") (pintype "passive"))
      (node (ref "C30") (pin "1") (pinfunction "1_1") (pintype "passive"))
      (node (ref "U$1") (pin "TX1") (pinfunction "TX1_TX1") (pintype "bidirectional"))
    )
    (net (code "59") (name "Net-(IC1-IN)") (class "Default")
      (node (ref "C2") (pin "+") (pinfunction "+_+") (pintype "passive"))
      (node (ref "IC1") (pin "3") (pinfunction "IN_3") (pintype "input"))
      (node (ref "T1") (pin "2") (pinfunction "S_2") (pintype "passive"))
    )
    (net (code "60") (name "Net-(J1-D+)") (class "Default")
      (node (ref "J1") (pin "3") (pinfunction "D+_3") (pintype "bidirectional"))
      (node (ref "R12") (pin "1") (pinfunction "1_1") (pintype "passive"))
    )
    (net (code "61") (name "Net-(J1-D-)") (class "Default")
      (node (ref "J1") (pin "4") (pinfunction "D-_4") (pintype "bidirectional"))
      (node (ref "R11") (pin "1") (pinfunction "1_1") (pintype "passive"))
    )
    (net (code "62") (name "Net-(J1-SH1)") (class "Default")
      (node (ref "J1") (pin "6") (pinfunction "SH1_6") (pintype "passive"))
      (node (ref "J1") (pin "7") (pinfunction "SH2_7") (pintype "passive"))
      (node (ref "J1") (pin "8") (pinfunction "SH3_8") (pintype "passive"))
      (node (ref "J1") (pin "9") (pinfunction "SH4_9") (pintype "passive"))
      (node (ref "R3") (pin "2") (pinfunction "2_2") (pintype "passive"))
    )
    (net (code "63") (name "Net-(J1-VBUS)") (class "Default")
      (node (ref "F1") (pin "1") (pinfunction "1_1") (pintype "bidirectional"))
      (node (ref "J1") (pin "5") (pinfunction "VBUS_5") (pintype "power_in"))
    )
    (net (code "64") (name "Net-(RP1A-2)") (class "Default")
      (node (ref "13") (pin "A") (pinfunction "A_A") (pintype "passive"))
      (node (ref "RP1") (pin "8") (pinfunction "2_8") (pintype "passive"))
    )
    (net (code "65") (name "Net-(RP1B-2)") (class "Default")
      (node (ref "ON") (pin "C") (pinfunction "C_C") (pintype "passive"))
      (node (ref "RP1") (pin "7") (pinfunction "2_7") (pintype "passive"))
    )
    (net (code "66") (name "Net-(RP1C-2)") (class "Default")
      (node (ref "RP1") (pin "6") (pinfunction "2_6") (pintype "passive"))
      (node (ref "TX") (pin "C") (pinfunction "C_C") (pintype "passive"))
    )
    (net (code "67") (name "Net-(RP1D-2)") (class "Default")
      (node (ref "RP1") (pin "5") (pinfunction "2_5") (pintype "passive"))
      (node (ref "RX") (pin "C") (pinfunction "C_C") (pintype "passive"))
    )
    (net (code "68") (name "Net-(U1-UCAP)") (class "Default")
      (node (ref "C23") (pin "1") (pinfunction "1_1") (pintype "passive"))
      (node (ref "U1") (pin "6") (pinfunction "UCAP_6") (pintype "passive"))
      (node (ref "U5") (pin "6") (pinfunction "UCAP_6") (pintype "passive"))
    )
    (net (code "69") (name "Net-(U3-OE)") (class "Default")
      (node (ref "R2") (pin "2") (pinfunction "2_2") (pintype "passive"))
      (node (ref "U3") (pin "10") (pinfunction "OE_10") (pintype "bidirectional"))
    )
    (net (code "70") (name "Net-(U4-RX)") (class "Default")
      (node (ref "C18") (pin "2") (pinfunction "2_2") (pintype "passive"))
      (node (ref "R5") (pin "1") (pinfunction "1_1") (pintype "passive"))
      (node (ref "U4") (pin "10") (pinfunction "RX_10") (pintype "bidirectional"))
    )
    (net (code "71") (name "Net-(U4-TX1)") (class "Default")
      (node (ref "L2") (pin "2") (pinfunction "2_2") (pintype "passive"))
      (node (ref "U4") (pin "4") (pinfunction "TX1_4") (pintype "bidirectional"))
    )
    (net (code "72") (name "Net-(U4-TX2)") (class "Default")
      (node (ref "L3") (pin "2") (pinfunction "2_2") (pintype "passive"))
      (node (ref "U4") (pin "6") (pinfunction "TX2_6") (pintype "bidirectional"))
    )
    (net (code "73") (name "Net-(U4-VMID)") (class "Default")
      (node (ref "C17") (pin "2") (pinfunction "2_2") (pintype "passive"))
      (node (ref "R5") (pin "2") (pinfunction "2_2") (pintype "passive"))
      (node (ref "U4") (pin "9") (pinfunction "VMID_9") (pintype "bidirectional"))
    )
    (net (code "74") (name "Net-(U4-XTAL1)") (class "Default")
      (node (ref "C15") (pin "2") (pinfunction "2_2") (pintype "passive"))
      (node (ref "U4") (pin "14") (pinfunction "XTAL1_14") (pintype "bidirectional"))
      (node (ref "Y2") (pin "1") (pinfunction "1_1") (pintype "passive"))
    )
    (net (code "75") (name "Net-(U4-XTAL2)") (class "Default")
      (node (ref "C11") (pin "2") (pinfunction "2_2") (pintype "passive"))
      (node (ref "U4") (pin "15") (pinfunction "XTAL2_15") (pintype "bidirectional"))
      (node (ref "Y2") (pin "2") (pinfunction "2_2") (pintype "passive"))
    )
    (net (code "76") (name "VIN") (class "Default")
      (node (ref "D1") (pin "C") (pinfunction "C_C") (pintype "passive"))
      (node (ref "EXTPOWER") (pin "2") (pinfunction "2_2") (pintype "power_in"))
      (node (ref "JP4") (pin "6") (pinfunction "6_6") (pintype "passive"))
      (node (ref "R1") (pin "2") (pinfunction "2_2") (pintype "passive"))
      (node (ref "T1") (pin "1") (pinfunction "D_1") (pintype "passive"))
      (node (ref "T2") (pin "3") (pinfunction "G_3") (pintype "passive"))
    )
    (net (code "77") (name "VUSB") (class "Default")
      (node (ref "C5") (pin "2") (pinfunction "2_2") (pintype "passive"))
      (node (ref "F1") (pin "2") (pinfunction "2_2") (pintype "bidirectional"))
      (node (ref "T2") (pin "1") (pinfunction "D_1") (pintype "passive"))
      (node (ref "U1") (pin "7") (pinfunction "VBUS_7") (pintype "input"))
      (node (ref "U5") (pin "7") (pinfunction "VBUS_7") (pintype "input"))
    )
    (net (code "78") (name "unconnected-(J1-ID-Pad2)") (class "Default")
      (node (ref "J1") (pin "2") (pinfunction "ID_2") (pintype "bidirectional"))
    )
    (net (code "79") (name "unconnected-(U$1-P$1-PadP$10)") (class "Default")
      (node (ref "U$1") (pin "P$10") (pinfunction "P$1_P$10") (pintype "no_connect"))
    )
    (net (code "80") (name "unconnected-(U$1-P$2-PadP$11)") (class "Default")
      (node (ref "U$1") (pin "P$11") (pinfunction "P$2_P$11") (pintype "no_connect"))
    )
    (net (code "81") (name "unconnected-(U$1-P$3-PadP$9)") (class "Default")
      (node (ref "U$1") (pin "P$9") (pinfunction "P$3_P$9") (pintype "no_connect"))
    )
    (net (code "82") (name "unconnected-(U$1-P$4-PadP$8)") (class "Default")
      (node (ref "U$1") (pin "P$8") (pinfunction "P$4_P$8") (pintype "no_connect"))
    )
    (net (code "83") (name "unconnected-(U$1-P$5-PadP$7)") (class "Default")
      (node (ref "U$1") (pin "P$7") (pinfunction "P$5_P$7") (pintype "no_connect"))
    )
    (net (code "84") (name "unconnected-(U$1-P$7-PadP$5)") (class "Default")
      (node (ref "U$1") (pin "P$5") (pinfunction "P$7_P$5") (pintype "no_connect"))
    )
    (net (code "85") (name "unconnected-(U$1-P$8-PadP$4)") (class "Default")
      (node (ref "U$1") (pin "P$4") (pinfunction "P$8_P$4") (pintype "no_connect"))
    )
    (net (code "86") (name "unconnected-(U$1-PadP$6)") (class "Default")
      (node (ref "U$1") (pin "P$6") (pinfunction "P$6_P$6") (pintype "no_connect"))
    )
    (net (code "87") (name "unconnected-(U2-NC{slash}FB-Pad4)") (class "Default")
      (node (ref "U2") (pin "4") (pinfunction "NC/FB_4") (pintype "passive"))
    )
    (net (code "88") (name "unconnected-(U3-A1-Pad1)") (class "Default")
      (node (ref "U3") (pin "1") (pinfunction "A1_1") (pintype "bidirectional"))
    )
    (net (code "89") (name "unconnected-(U3-A2-Pad3)") (class "Default")
      (node (ref "U3") (pin "3") (pinfunction "A2_3") (pintype "bidirectional"))
    )
    (net (code "90") (name "unconnected-(U3-A7-Pad8)") (class "Default")
      (node (ref "U3") (pin "8") (pinfunction "A7_8") (pintype "bidirectional"))
    )
    (net (code "91") (name "unconnected-(U3-A8-Pad9)") (class "Default")
      (node (ref "U3") (pin "9") (pinfunction "A8_9") (pintype "bidirectional"))
    )
    (net (code "92") (name "unconnected-(U3-B1-Pad20)") (class "Default")
      (node (ref "U3") (pin "20") (pinfunction "B1_20") (pintype "bidirectional"))
    )
    (net (code "93") (name "unconnected-(U3-B2-Pad18)") (class "Default")
      (node (ref "U3") (pin "18") (pinfunction "B2_18") (pintype "bidirectional"))
    )
    (net (code "94") (name "unconnected-(U3-B7-Pad13)") (class "Default")
      (node (ref "U3") (pin "13") (pinfunction "B7_13") (pintype "bidirectional"))
    )
    (net (code "95") (name "unconnected-(U3-B8-Pad12)") (class "Default")
      (node (ref "U3") (pin "12") (pinfunction "B8_12") (pintype "bidirectional"))
    )
    (net (code "96") (name "unconnected-(U4-DVDD-Pad39)") (class "Default")
      (node (ref "U4") (pin "39") (pinfunction "DVDD_39") (pintype "bidirectional"))
    )
    (net (code "97") (name "unconnected-(U4-LOADMOD-Pad2)") (class "Default")
      (node (ref "U4") (pin "2") (pinfunction "LOADMOD_2") (pintype "bidirectional"))
    )
    (net (code "98") (name "unconnected-(U4-MISO-Pad29)") (class "Default")
      (node (ref "U4") (pin "29") (pinfunction "MISO_29") (pintype "bidirectional"))
    )
    (net (code "99") (name "unconnected-(U4-NC1-Pad20)") (class "Default")
      (node (ref "U4") (pin "20") (pinfunction "NC1_20") (pintype "bidirectional"))
    )
    (net (code "100") (name "unconnected-(U4-NC2-Pad21)") (class "Default")
      (node (ref "U4") (pin "21") (pinfunction "NC2_21") (pintype "bidirectional"))
    )
    (net (code "101") (name "unconnected-(U4-NC3-Pad22)") (class "Default")
      (node (ref "U4") (pin "22") (pinfunction "NC3_22") (pintype "bidirectional"))
    )
    (net (code "102") (name "unconnected-(U4-SCK-Pad30)") (class "Default")
      (node (ref "U4") (pin "30") (pinfunction "SCK_30") (pintype "bidirectional"))
    )
    (net (code "103") (name "unconnected-(X1-GND-Pad2)") (class "Default")
      (node (ref "X1") (pin "2") (pinfunction "GND_2") (pintype "passive"))
    )
  )
)
